# Prepheral.net
KiCad netlist of a schematic drawn in Altium Designer
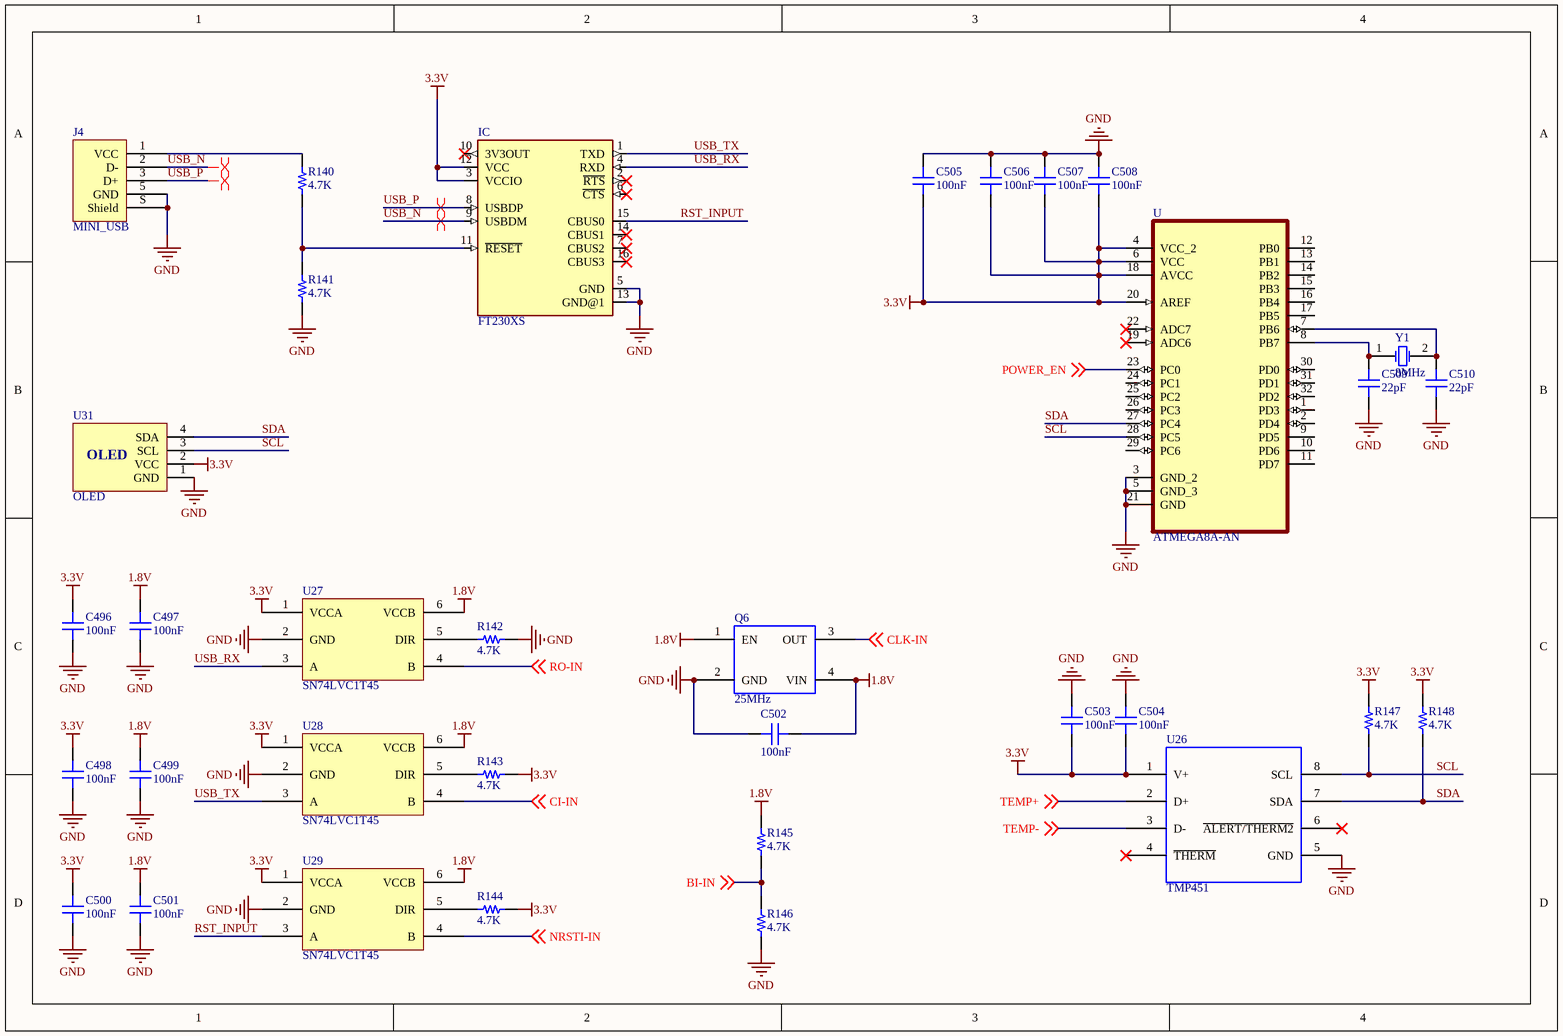
[diagram p0: Prepheral.SchDoc]

(export (version "E")
  (design (tool "Eeschema 10.0.6"))
  (components
    (comp (ref "C496") (value "100nF") (footprint "CAP-SMD-0603") (libsource (lib "Miner_8TH") (part "CAP")))
    (comp (ref "C497") (value "100nF") (footprint "CAP-SMD-0603") (libsource (lib "Miner_8TH") (part "CAP")))
    (comp (ref "C498") (value "100nF") (footprint "CAP-SMD-0603") (libsource (lib "Miner_8TH") (part "CAP")))
    (comp (ref "C499") (value "100nF") (footprint "CAP-SMD-0603") (libsource (lib "Miner_8TH") (part "CAP")))
    (comp (ref "C500") (value "100nF") (footprint "CAP-SMD-0603") (libsource (lib "Miner_8TH") (part "CAP")))
    (comp (ref "C501") (value "100nF") (footprint "CAP-SMD-0603") (libsource (lib "Miner_8TH") (part "CAP")))
    (comp (ref "C502") (value "100nF") (footprint "CAP_SMD_0805") (libsource (lib "Miner_8TH") (part "CAP")))
    (comp (ref "C503") (value "100nF") (footprint "CAP_SMD_0805") (libsource (lib "Miner_8TH") (part "CAP")))
    (comp (ref "C504") (value "100nF") (footprint "CAP_SMD_0805") (libsource (lib "Miner_8TH") (part "CAP")))
    (comp (ref "C505") (value "100nF") (footprint "CAP_SMD_0805") (libsource (lib "Miner_8TH") (part "CAP")))
    (comp (ref "C506") (value "100nF") (footprint "CAP_SMD_0805") (libsource (lib "Miner_8TH") (part "CAP")))
    (comp (ref "C507") (value "100nF") (footprint "CAP_SMD_0805") (libsource (lib "Miner_8TH") (part "CAP")))
    (comp (ref "C508") (value "100nF") (footprint "CAP_SMD_0805") (libsource (lib "Miner_8TH") (part "CAP")))
    (comp (ref "C509") (value "22pF") (footprint "CAP_SMD_0805") (libsource (lib "Miner_8TH") (part "CAP")))
    (comp (ref "C510") (value "22pF") (footprint "CAP_SMD_0805") (libsource (lib "Miner_8TH") (part "CAP")))
    (comp (ref "IC")
      (value "FT230XS")
      (footprint "SSOP16")
      (description "USB Bridge, USB to UART USB 2.0 UART Interface 16-SSOP")
      (fields (field (name "MF") "FTDI, Future"))
      (libsource (lib "Miner_8TH") (part "FT230XS"))
    )
    (comp (ref "J4")
      (value "MINI_USB")
      (footprint "Mini_usb")
      (libsource (lib "Miner_8TH") (part "MINI_USB"))
    )
    (comp (ref "Q6") (value "25MHz") (footprint "XTALL") (libsource (lib "Miner_8TH") (part "OSCILLATOR")))
    (comp (ref "R140") (value "4.7K") (footprint "RES-SMD-0603") (libsource (lib "Miner_8TH") (part "RES")))
    (comp (ref "R141") (value "4.7K") (footprint "RES-SMD-0603") (libsource (lib "Miner_8TH") (part "RES")))
    (comp (ref "R142") (value "4.7K") (footprint "RES-SMD-0603") (libsource (lib "Miner_8TH") (part "RES")))
    (comp (ref "R143") (value "4.7K") (footprint "RES-SMD-0603") (libsource (lib "Miner_8TH") (part "RES")))
    (comp (ref "R144") (value "4.7K") (footprint "RES-SMD-0603") (libsource (lib "Miner_8TH") (part "RES")))
    (comp (ref "R145") (value "4.7K") (footprint "RES-SMD-0603") (libsource (lib "Miner_8TH") (part "RES")))
    (comp (ref "R146") (value "4.7K") (footprint "RES-SMD-0603") (libsource (lib "Miner_8TH") (part "RES")))
    (comp (ref "R147") (value "4.7K") (footprint "RES-SMD-0603") (libsource (lib "Miner_8TH") (part "RES")))
    (comp (ref "R148") (value "4.7K") (footprint "RES-SMD-0603") (libsource (lib "Miner_8TH") (part "RES")))
    (comp (ref "U")
      (value "ATMEGA8A-AN")
      (footprint "QFP80P900X900X120-32N")
      (description "AVR AVRÂ® ATmega Microcontroller IC 8-Bit 16MHz 8KB (4K x 16) FLASH 32-TQFP (7x7)")
      (fields (field (name "MF") "Microchip"))
      (libsource (lib "Miner_8TH") (part "ATMEGA8A-AN"))
    )
    (comp (ref "U26")
      (value "TMP451")
      (footprint "SON50P200X200X80-9N")
      (libsource (lib "Miner_8TH") (part "TMP451"))
    )
    (comp (ref "U27")
      (value "SN74LVC1T45")
      (footprint "SOT23-6PIN")
      (libsource (lib "Miner_8TH") (part "SN74LVC1T45"))
    )
    (comp (ref "U28")
      (value "SN74LVC1T45")
      (footprint "SOT23-6PIN")
      (libsource (lib "Miner_8TH") (part "SN74LVC1T45"))
    )
    (comp (ref "U29")
      (value "SN74LVC1T45")
      (footprint "SOT23-6PIN")
      (libsource (lib "Miner_8TH") (part "SN74LVC1T45"))
    )
    (comp (ref "U31") (value "OLED") (footprint "OLED") (libsource (lib "Miner_8TH") (part "OLED")))
    (comp (ref "Y1")
      (value "8MHz")
      (footprint "XTAL_SMD")
      (description "Crystal Oscillator")
      (fields (field (name "PUBLISHER") "Altium Limited"))
      (libsource (lib "Miner_8TH") (part "XTAL"))
    )
  )
  (nets
    (net (code "1") (name "/RST_INPUT") (class "Default")
      (node (ref "IC") (pin "15") (pinfunction "CBUS0_15") (pintype "bidirectional"))
      (node (ref "U29") (pin "3") (pinfunction "A_3") (pintype "passive"))
    )
    (net (code "2") (name "/SCL") (class "Default")
      (node (ref "R147") (pin "1") (pinfunction "1_1") (pintype "passive"))
      (node (ref "U") (pin "28") (pinfunction "PC5_28") (pintype "bidirectional"))
      (node (ref "U26") (pin "8") (pinfunction "SCL_8") (pintype "passive"))
      (node (ref "U31") (pin "3") (pinfunction "SCL_3") (pintype "passive"))
    )
    (net (code "3") (name "/SDA") (class "Default")
      (node (ref "R148") (pin "1") (pinfunction "1_1") (pintype "passive"))
      (node (ref "U") (pin "27") (pinfunction "PC4_27") (pintype "bidirectional"))
      (node (ref "U26") (pin "7") (pinfunction "SDA_7") (pintype "passive"))
      (node (ref "U31") (pin "4") (pinfunction "SDA_4") (pintype "passive"))
    )
    (net (code "4") (name "/USB_N") (class "Default")
      (node (ref "IC") (pin "9") (pinfunction "USBDM_9") (pintype "input"))
      (node (ref "J4") (pin "2") (pinfunction "D-_2") (pintype "passive"))
    )
    (net (code "5") (name "/USB_P") (class "Default")
      (node (ref "IC") (pin "8") (pinfunction "USBDP_8") (pintype "input"))
      (node (ref "J4") (pin "3") (pinfunction "D+_3") (pintype "passive"))
    )
    (net (code "6") (name "/USB_RX") (class "Default")
      (node (ref "IC") (pin "4") (pinfunction "RXD_4") (pintype "input"))
      (node (ref "U27") (pin "3") (pinfunction "A_3") (pintype "passive"))
    )
    (net (code "7") (name "/USB_TX") (class "Default")
      (node (ref "IC") (pin "1") (pinfunction "TXD_1") (pintype "output"))
      (node (ref "U28") (pin "3") (pinfunction "A_3") (pintype "passive"))
    )
    (net (code "8") (name "1.8V") (class "Default")
      (node (ref "C497") (pin "2") (pinfunction "2_2") (pintype "passive"))
      (node (ref "C499") (pin "2") (pinfunction "2_2") (pintype "passive"))
      (node (ref "C501") (pin "2") (pinfunction "2_2") (pintype "passive"))
      (node (ref "C502") (pin "2") (pinfunction "2_2") (pintype "passive"))
      (node (ref "Q6") (pin "1") (pinfunction "EN_1") (pintype "passive"))
      (node (ref "Q6") (pin "4") (pinfunction "VIN_4") (pintype "passive"))
      (node (ref "R145") (pin "1") (pinfunction "1_1") (pintype "passive"))
      (node (ref "U27") (pin "6") (pinfunction "VCCB_6") (pintype "passive"))
      (node (ref "U28") (pin "6") (pinfunction "VCCB_6") (pintype "passive"))
      (node (ref "U29") (pin "6") (pinfunction "VCCB_6") (pintype "passive"))
    )
    (net (code "9") (name "3.3V") (class "Default")
      (node (ref "C496") (pin "2") (pinfunction "2_2") (pintype "passive"))
      (node (ref "C498") (pin "2") (pinfunction "2_2") (pintype "passive"))
      (node (ref "C500") (pin "2") (pinfunction "2_2") (pintype "passive"))
      (node (ref "C503") (pin "1") (pinfunction "1_1") (pintype "passive"))
      (node (ref "C504") (pin "1") (pinfunction "1_1") (pintype "passive"))
      (node (ref "C505") (pin "1") (pinfunction "1_1") (pintype "passive"))
      (node (ref "C506") (pin "1") (pinfunction "1_1") (pintype "passive"))
      (node (ref "C507") (pin "1") (pinfunction "1_1") (pintype "passive"))
      (node (ref "C508") (pin "1") (pinfunction "1_1") (pintype "passive"))
      (node (ref "IC") (pin "12") (pinfunction "VCC_12") (pintype "power_in"))
      (node (ref "IC") (pin "3") (pinfunction "VCCIO_3") (pintype "power_in"))
      (node (ref "R143") (pin "1") (pinfunction "1_1") (pintype "passive"))
      (node (ref "R144") (pin "1") (pinfunction "1_1") (pintype "passive"))
      (node (ref "R147") (pin "2") (pinfunction "2_2") (pintype "passive"))
      (node (ref "R148") (pin "2") (pinfunction "2_2") (pintype "passive"))
      (node (ref "U") (pin "18") (pinfunction "AVCC_18") (pintype "power_in"))
      (node (ref "U") (pin "20") (pinfunction "AREF_20") (pintype "input"))
      (node (ref "U") (pin "4") (pinfunction "VCC_2_4") (pintype "power_in"))
      (node (ref "U") (pin "6") (pinfunction "VCC_6") (pintype "power_in"))
      (node (ref "U26") (pin "1") (pinfunction "V+_1") (pintype "passive"))
      (node (ref "U27") (pin "1") (pinfunction "VCCA_1") (pintype "passive"))
      (node (ref "U28") (pin "1") (pinfunction "VCCA_1") (pintype "passive"))
      (node (ref "U29") (pin "1") (pinfunction "VCCA_1") (pintype "passive"))
      (node (ref "U31") (pin "2") (pinfunction "VCC_2") (pintype "passive"))
    )
    (net (code "10") (name "BI-IN") (class "Default")
      (node (ref "R145") (pin "2") (pinfunction "2_2") (pintype "passive"))
      (node (ref "R146") (pin "1") (pinfunction "1_1") (pintype "passive"))
    )
    (net (code "11") (name "CI-IN") (class "Default")
      (node (ref "U28") (pin "4") (pinfunction "B_4") (pintype "passive"))
    )
    (net (code "12") (name "CLK-IN") (class "Default")
      (node (ref "Q6") (pin "3") (pinfunction "OUT_3") (pintype "passive"))
    )
    (net (code "13") (name "GND") (class "Default")
      (node (ref "C496") (pin "1") (pinfunction "1_1") (pintype "passive"))
      (node (ref "C497") (pin "1") (pinfunction "1_1") (pintype "passive"))
      (node (ref "C498") (pin "1") (pinfunction "1_1") (pintype "passive"))
      (node (ref "C499") (pin "1") (pinfunction "1_1") (pintype "passive"))
      (node (ref "C500") (pin "1") (pinfunction "1_1") (pintype "passive"))
      (node (ref "C501") (pin "1") (pinfunction "1_1") (pintype "passive"))
      (node (ref "C502") (pin "1") (pinfunction "1_1") (pintype "passive"))
      (node (ref "C503") (pin "2") (pinfunction "2_2") (pintype "passive"))
      (node (ref "C504") (pin "2") (pinfunction "2_2") (pintype "passive"))
      (node (ref "C505") (pin "2") (pinfunction "2_2") (pintype "passive"))
      (node (ref "C506") (pin "2") (pinfunction "2_2") (pintype "passive"))
      (node (ref "C507") (pin "2") (pinfunction "2_2") (pintype "passive"))
      (node (ref "C508") (pin "2") (pinfunction "2_2") (pintype "passive"))
      (node (ref "C509") (pin "1") (pinfunction "1_1") (pintype "passive"))
      (node (ref "C510") (pin "1") (pinfunction "1_1") (pintype "passive"))
      (node (ref "IC") (pin "13") (pinfunction "GND@1_13") (pintype "power_in"))
      (node (ref "IC") (pin "5") (pinfunction "GND_5") (pintype "power_in"))
      (node (ref "J4") (pin "5") (pinfunction "GND_5") (pintype "passive"))
      (node (ref "J4") (pin "S") (pinfunction "Shield_S") (pintype "passive"))
      (node (ref "Q6") (pin "2") (pinfunction "GND_2") (pintype "passive"))
      (node (ref "R141") (pin "1") (pinfunction "1_1") (pintype "passive"))
      (node (ref "R142") (pin "1") (pinfunction "1_1") (pintype "passive"))
      (node (ref "R146") (pin "2") (pinfunction "2_2") (pintype "passive"))
      (node (ref "U") (pin "21") (pinfunction "GND_21") (pintype "passive"))
      (node (ref "U") (pin "3") (pinfunction "GND_2_3") (pintype "passive"))
      (node (ref "U") (pin "5") (pinfunction "GND_3_5") (pintype "passive"))
      (node (ref "U26") (pin "5") (pinfunction "GND_5") (pintype "passive"))
      (node (ref "U27") (pin "2") (pinfunction "GND_2") (pintype "passive"))
      (node (ref "U28") (pin "2") (pinfunction "GND_2") (pintype "passive"))
      (node (ref "U29") (pin "2") (pinfunction "GND_2") (pintype "passive"))
      (node (ref "U31") (pin "1") (pinfunction "GND_1") (pintype "passive"))
    )
    (net (code "14") (name "NRSTI-IN") (class "Default")
      (node (ref "U29") (pin "4") (pinfunction "B_4") (pintype "passive"))
    )
    (net (code "15") (name "Net-(IC-~{RESET})") (class "Default")
      (node (ref "IC") (pin "11") (pinfunction "~{RESET}_11") (pintype "input"))
      (node (ref "R140") (pin "1") (pinfunction "1_1") (pintype "passive"))
      (node (ref "R141") (pin "2") (pinfunction "2_2") (pintype "passive"))
    )
    (net (code "16") (name "Net-(J4-VCC)") (class "Default")
      (node (ref "J4") (pin "1") (pinfunction "VCC_1") (pintype "passive"))
      (node (ref "R140") (pin "2") (pinfunction "2_2") (pintype "passive"))
    )
    (net (code "17") (name "Net-(U-PB6)") (class "Default")
      (node (ref "C510") (pin "2") (pinfunction "2_2") (pintype "passive"))
      (node (ref "U") (pin "7") (pinfunction "PB6_7") (pintype "bidirectional"))
      (node (ref "Y1") (pin "2") (pinfunction "OSC2_2") (pintype "passive"))
    )
    (net (code "18") (name "Net-(U-PB7)") (class "Default")
      (node (ref "C509") (pin "2") (pinfunction "2_2") (pintype "passive"))
      (node (ref "U") (pin "8") (pinfunction "PB7_8") (pintype "passive"))
      (node (ref "Y1") (pin "1") (pinfunction "OSC1_1") (pintype "passive"))
    )
    (net (code "19") (name "Net-(U27-DIR)") (class "Default")
      (node (ref "R142") (pin "2") (pinfunction "2_2") (pintype "passive"))
      (node (ref "U27") (pin "5") (pinfunction "DIR_5") (pintype "passive"))
    )
    (net (code "20") (name "Net-(U28-DIR)") (class "Default")
      (node (ref "R143") (pin "2") (pinfunction "2_2") (pintype "passive"))
      (node (ref "U28") (pin "5") (pinfunction "DIR_5") (pintype "passive"))
    )
    (net (code "21") (name "Net-(U29-DIR)") (class "Default")
      (node (ref "R144") (pin "2") (pinfunction "2_2") (pintype "passive"))
      (node (ref "U29") (pin "5") (pinfunction "DIR_5") (pintype "passive"))
    )
    (net (code "22") (name "POWER_EN") (class "Default")
      (node (ref "U") (pin "23") (pinfunction "PC0_23") (pintype "bidirectional"))
    )
    (net (code "23") (name "RO-IN") (class "Default")
      (node (ref "U27") (pin "4") (pinfunction "B_4") (pintype "passive"))
    )
    (net (code "24") (name "TEMP+") (class "Default")
      (node (ref "U26") (pin "2") (pinfunction "D+_2") (pintype "passive"))
    )
    (net (code "25") (name "TEMP-") (class "Default")
      (node (ref "U26") (pin "3") (pinfunction "D-_3") (pintype "passive"))
    )
    (net (code "26") (name "unconnected-(IC-3V3OUT-Pad10)") (class "Default")
      (node (ref "IC") (pin "10") (pinfunction "3V3OUT_10") (pintype "output+no_connect"))
    )
    (net (code "27") (name "unconnected-(IC-CBUS1-Pad14)") (class "Default")
      (node (ref "IC") (pin "14") (pinfunction "CBUS1_14") (pintype "bidirectional+no_connect"))
    )
    (net (code "28") (name "unconnected-(IC-CBUS2-Pad7)") (class "Default")
      (node (ref "IC") (pin "7") (pinfunction "CBUS2_7") (pintype "bidirectional+no_connect"))
    )
    (net (code "29") (name "unconnected-(IC-CBUS3-Pad16)") (class "Default")
      (node (ref "IC") (pin "16") (pinfunction "CBUS3_16") (pintype "bidirectional+no_connect"))
    )
    (net (code "30") (name "unconnected-(IC-~{CTS}-Pad6)") (class "Default")
      (node (ref "IC") (pin "6") (pinfunction "~{CTS}_6") (pintype "input+no_connect"))
    )
    (net (code "31") (name "unconnected-(IC-~{RTS}-Pad2)") (class "Default")
      (node (ref "IC") (pin "2") (pinfunction "~{RTS}_2") (pintype "output+no_connect"))
    )
    (net (code "32") (name "unconnected-(U-ADC6-Pad19)") (class "Default")
      (node (ref "U") (pin "19") (pinfunction "ADC6_19") (pintype "input+no_connect"))
    )
    (net (code "33") (name "unconnected-(U-ADC7-Pad22)") (class "Default")
      (node (ref "U") (pin "22") (pinfunction "ADC7_22") (pintype "input+no_connect"))
    )
    (net (code "34") (name "unconnected-(U-PB0-Pad12)") (class "Default")
      (node (ref "U") (pin "12") (pinfunction "PB0_12") (pintype "passive"))
    )
    (net (code "35") (name "unconnected-(U-PB1-Pad13)") (class "Default")
      (node (ref "U") (pin "13") (pinfunction "PB1_13") (pintype "passive"))
    )
    (net (code "36") (name "unconnected-(U-PB2-Pad14)") (class "Default")
      (node (ref "U") (pin "14") (pinfunction "PB2_14") (pintype "passive"))
    )
    (net (code "37") (name "unconnected-(U-PB3-Pad15)") (class "Default")
      (node (ref "U") (pin "15") (pinfunction "PB3_15") (pintype "passive"))
    )
    (net (code "38") (name "unconnected-(U-PB4-Pad16)") (class "Default")
      (node (ref "U") (pin "16") (pinfunction "PB4_16") (pintype "passive"))
    )
    (net (code "39") (name "unconnected-(U-PB5-Pad17)") (class "Default")
      (node (ref "U") (pin "17") (pinfunction "PB5_17") (pintype "passive"))
    )
    (net (code "40") (name "unconnected-(U-PC1-Pad24)") (class "Default")
      (node (ref "U") (pin "24") (pinfunction "PC1_24") (pintype "bidirectional"))
    )
    (net (code "41") (name "unconnected-(U-PC2-Pad25)") (class "Default")
      (node (ref "U") (pin "25") (pinfunction "PC2_25") (pintype "bidirectional"))
    )
    (net (code "42") (name "unconnected-(U-PC3-Pad26)") (class "Default")
      (node (ref "U") (pin "26") (pinfunction "PC3_26") (pintype "bidirectional"))
    )
    (net (code "43") (name "unconnected-(U-PC6-Pad29)") (class "Default")
      (node (ref "U") (pin "29") (pinfunction "PC6_29") (pintype "bidirectional"))
    )
    (net (code "44") (name "unconnected-(U-PD0-Pad30)") (class "Default")
      (node (ref "U") (pin "30") (pinfunction "PD0_30") (pintype "bidirectional"))
    )
    (net (code "45") (name "unconnected-(U-PD1-Pad31)") (class "Default")
      (node (ref "U") (pin "31") (pinfunction "PD1_31") (pintype "bidirectional"))
    )
    (net (code "46") (name "unconnected-(U-PD2-Pad32)") (class "Default")
      (node (ref "U") (pin "32") (pinfunction "PD2_32") (pintype "bidirectional"))
    )
    (net (code "47") (name "unconnected-(U-PD3-Pad1)") (class "Default")
      (node (ref "U") (pin "1") (pinfunction "PD3_1") (pintype "bidirectional"))
    )
    (net (code "48") (name "unconnected-(U-PD4-Pad2)") (class "Default")
      (node (ref "U") (pin "2") (pinfunction "PD4_2") (pintype "bidirectional"))
    )
    (net (code "49") (name "unconnected-(U-PD5-Pad9)") (class "Default")
      (node (ref "U") (pin "9") (pinfunction "PD5_9") (pintype "passive"))
    )
    (net (code "50") (name "unconnected-(U-PD6-Pad10)") (class "Default")
      (node (ref "U") (pin "10") (pinfunction "PD6_10") (pintype "passive"))
    )
    (net (code "51") (name "unconnected-(U-PD7-Pad11)") (class "Default")
      (node (ref "U") (pin "11") (pinfunction "PD7_11") (pintype "passive"))
    )
    (net (code "52") (name "unconnected-(U26-~{ALERT{slash}THERM2}-Pad6)") (class "Default")
      (node (ref "U26") (pin "6") (pinfunction "~{ALERT/THERM2}_6") (pintype "passive+no_connect"))
    )
    (net (code "53") (name "unconnected-(U26-~{THERM}-Pad4)") (class "Default")
      (node (ref "U26") (pin "4") (pinfunction "~{THERM}_4") (pintype "passive+no_connect"))
    )
  )
)
